# OpenFileWithEagle6_5.net
KiCad netlist of a schematic drawn in EAGLE
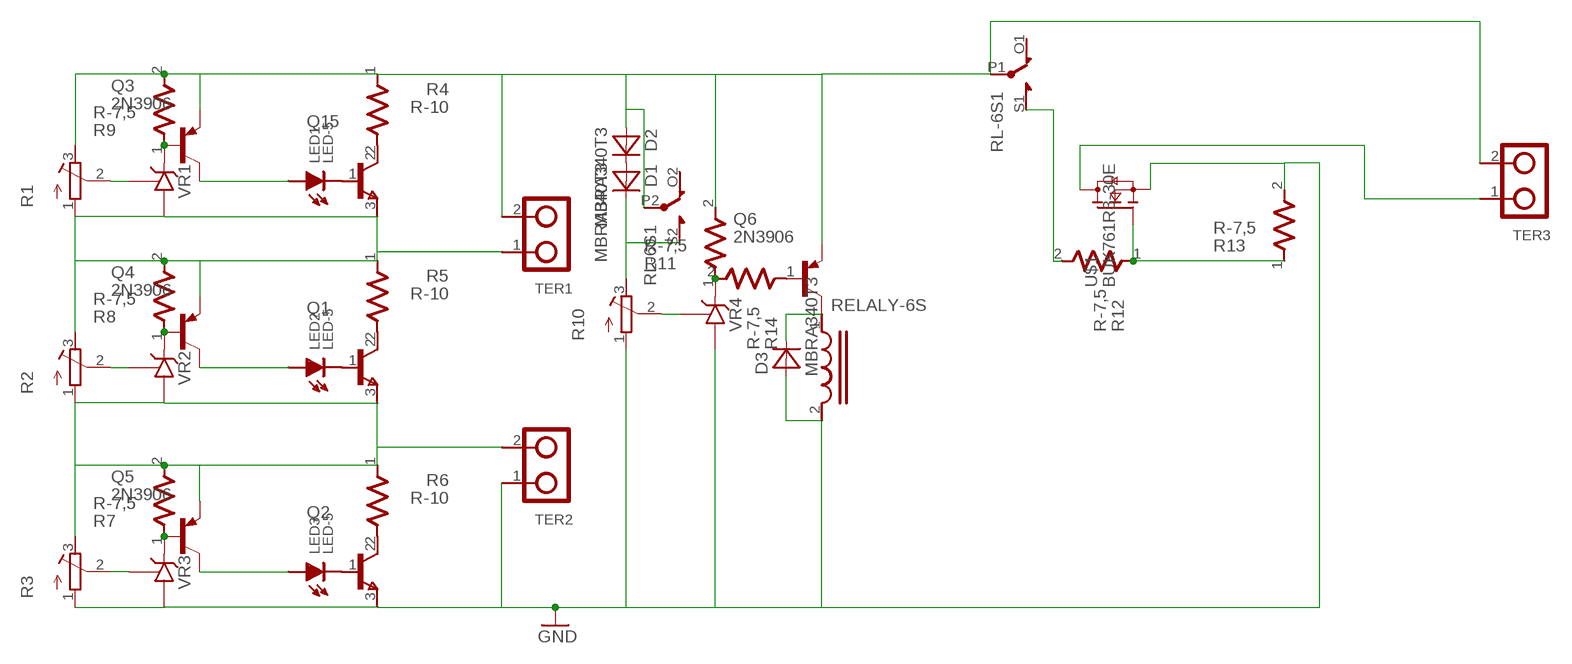
[diagram p0: schematic, sheet 1]

(export (version "E")
  (design (tool "Eeschema 10.0.6"))
  (components
    (comp (ref "D1")
      (value "MBRA340T3")
      (footprint "eagle-import:SMA")
      (libsource (lib "eagle-import") (part "MBRA340T3"))
    )
    (comp (ref "D2")
      (value "MBRA340T3")
      (footprint "eagle-import:SMA")
      (libsource (lib "eagle-import") (part "MBRA340T3"))
    )
    (comp (ref "D3")
      (value "MBRA340T3")
      (footprint "eagle-import:SMA")
      (libsource (lib "eagle-import") (part "MBRA340T3"))
    )
    (comp (ref "LED1")
      (value "LED-5")
      (footprint "eagle-import:LED5")
      (libsource (lib "eagle-import") (part "LED-5"))
    )
    (comp (ref "LED2")
      (value "LED-5")
      (footprint "eagle-import:LED5")
      (libsource (lib "eagle-import") (part "LED-5"))
    )
    (comp (ref "LED3")
      (value "LED-5")
      (footprint "eagle-import:LED5")
      (libsource (lib "eagle-import") (part "LED-5"))
    )
    (comp (ref "Q1")
      (value "C1815")
      (footprint "eagle-import:TO92L")
      (libsource (lib "eagle-import") (part "C1815"))
    )
    (comp (ref "Q2")
      (value "C1815")
      (footprint "eagle-import:TO92L")
      (libsource (lib "eagle-import") (part "C1815"))
    )
    (comp (ref "Q3")
      (value "2N3906")
      (footprint "eagle-import:TO92")
      (libsource (lib "eagle-import") (part "2N3906"))
    )
    (comp (ref "Q4")
      (value "2N3906")
      (footprint "eagle-import:TO92")
      (libsource (lib "eagle-import") (part "2N3906"))
    )
    (comp (ref "Q5")
      (value "2N3906")
      (footprint "eagle-import:TO92")
      (libsource (lib "eagle-import") (part "2N3906"))
    )
    (comp (ref "Q6")
      (value "2N3906")
      (footprint "eagle-import:TO92")
      (libsource (lib "eagle-import") (part "2N3906"))
    )
    (comp (ref "Q15")
      (value "C1815")
      (footprint "eagle-import:TO92L")
      (libsource (lib "eagle-import") (part "C1815"))
    )
    (comp (ref "R1")
      (value "R-TRIMM64W")
      (footprint "eagle-import:RTRIM64W")
      (libsource (lib "eagle-import") (part "R-TRIMM64W"))
    )
    (comp (ref "R2")
      (value "R-TRIMM64W")
      (footprint "eagle-import:RTRIM64W")
      (libsource (lib "eagle-import") (part "R-TRIMM64W"))
    )
    (comp (ref "R3")
      (value "R-TRIMM64W")
      (footprint "eagle-import:RTRIM64W")
      (libsource (lib "eagle-import") (part "R-TRIMM64W"))
    )
    (comp (ref "R4")
      (value "R-10")
      (footprint "eagle-import:R-10")
      (libsource (lib "eagle-import") (part "R-10"))
    )
    (comp (ref "R5")
      (value "R-10")
      (footprint "eagle-import:R-10")
      (libsource (lib "eagle-import") (part "R-10"))
    )
    (comp (ref "R6")
      (value "R-10")
      (footprint "eagle-import:R-10")
      (libsource (lib "eagle-import") (part "R-10"))
    )
    (comp (ref "R7")
      (value "R-7,5")
      (footprint "eagle-import:R-7,5")
      (libsource (lib "eagle-import") (part "R-7,5"))
    )
    (comp (ref "R8")
      (value "R-7,5")
      (footprint "eagle-import:R-7,5")
      (libsource (lib "eagle-import") (part "R-7,5"))
    )
    (comp (ref "R9")
      (value "R-7,5")
      (footprint "eagle-import:R-7,5")
      (libsource (lib "eagle-import") (part "R-7,5"))
    )
    (comp (ref "R10")
      (value "R-TRIMM64W")
      (footprint "eagle-import:RTRIM64W")
      (libsource (lib "eagle-import") (part "R-TRIMM64W"))
    )
    (comp (ref "R11")
      (value "R-7,5")
      (footprint "eagle-import:R-7,5")
      (libsource (lib "eagle-import") (part "R-7,5"))
    )
    (comp (ref "R12")
      (value "R-7,5")
      (footprint "eagle-import:R-7,5")
      (libsource (lib "eagle-import") (part "R-7,5"))
    )
    (comp (ref "R13")
      (value "R-7,5")
      (footprint "eagle-import:R-7,5")
      (libsource (lib "eagle-import") (part "R-7,5"))
    )
    (comp (ref "R14")
      (value "R-7,5")
      (footprint "eagle-import:R-7,5")
      (libsource (lib "eagle-import") (part "R-7,5"))
    )
    (comp (ref "RL-6S1")
      (value "RELALY-6S")
      (footprint "eagle-import:RELAY-6S")
      (libsource (lib "eagle-import") (part "RELALY-6S"))
    )
    (comp (ref "TER1")
      (value "DOMINO-2")
      (footprint "eagle-import:DOMI-2")
      (libsource (lib "eagle-import") (part "DOMINO-2"))
    )
    (comp (ref "TER2")
      (value "DOMINO-2")
      (footprint "eagle-import:DOMI-2")
      (libsource (lib "eagle-import") (part "DOMINO-2"))
    )
    (comp (ref "TER3")
      (value "DOMINO-2")
      (footprint "eagle-import:DOMI-2")
      (libsource (lib "eagle-import") (part "DOMINO-2"))
    )
    (comp (ref "U$1")
      (value "BUK761R3-30E")
      (footprint "eagle-import:SOT404")
      (libsource (lib "eagle-import") (part "BUK761R3-30E"))
    )
    (comp (ref "VR1")
      (value "TL431CLP")
      (footprint "eagle-import:TO92-CLP")
      (libsource (lib "eagle-import") (part "TL431CLP"))
    )
    (comp (ref "VR2")
      (value "TL431CLP")
      (footprint "eagle-import:TO92-CLP")
      (libsource (lib "eagle-import") (part "TL431CLP"))
    )
    (comp (ref "VR3")
      (value "TL431CLP")
      (footprint "eagle-import:TO92-CLP")
      (libsource (lib "eagle-import") (part "TL431CLP"))
    )
    (comp (ref "VR4")
      (value "TL431CLP")
      (footprint "eagle-import:TO92-CLP")
      (libsource (lib "eagle-import") (part "TL431CLP"))
    )
  )
  (nets
    (net (code "1") (name "GND") (class "Default")
      (node (ref "D3") (pin "A") (pinfunction "A_A") (pintype "passive"))
      (node (ref "Q2") (pin "3") (pinfunction "E_3") (pintype "passive"))
      (node (ref "R10") (pin "1") (pinfunction "A_1") (pintype "passive"))
      (node (ref "R13") (pin "2") (pinfunction "2_2") (pintype "passive"))
      (node (ref "R3") (pin "1") (pinfunction "A_1") (pintype "passive"))
      (node (ref "RL-6S1") (pin "2") (pinfunction "2_2") (pintype "bidirectional"))
      (node (ref "TER2") (pin "1") (pinfunction "1_1") (pintype "bidirectional"))
      (node (ref "U$1") (pin "3") (pinfunction "S_3") (pintype "passive"))
      (node (ref "VR3") (pin "A") (pinfunction "A_A") (pintype "passive"))
      (node (ref "VR4") (pin "A") (pinfunction "A_A") (pintype "passive"))
    )
    (net (code "2") (name "Net-(D1-PadA)") (class "Default")
      (node (ref "D1") (pin "A") (pinfunction "A_A") (pintype "passive"))
      (node (ref "D2") (pin "C") (pinfunction "C_C") (pintype "passive"))
    )
    (net (code "3") (name "Net-(Q1-B)") (class "Default")
      (node (ref "LED2") (pin "K") (pinfunction "K_K") (pintype "passive"))
      (node (ref "Q1") (pin "1") (pinfunction "B_1") (pintype "passive"))
    )
    (net (code "4") (name "Net-(Q1-C)") (class "Default")
      (node (ref "Q1") (pin "2") (pinfunction "C_2") (pintype "passive"))
      (node (ref "R5") (pin "2") (pinfunction "3_2") (pintype "passive"))
    )
    (net (code "5") (name "Net-(Q1-E)") (class "Default")
      (node (ref "Q1") (pin "3") (pinfunction "E_3") (pintype "passive"))
      (node (ref "Q5") (pin "3") (pinfunction "E_3") (pintype "passive"))
      (node (ref "R2") (pin "1") (pinfunction "A_1") (pintype "passive"))
      (node (ref "R3") (pin "3") (pinfunction "E_3") (pintype "passive"))
      (node (ref "R6") (pin "1") (pinfunction "1_1") (pintype "passive"))
      (node (ref "R7") (pin "2") (pinfunction "2_2") (pintype "passive"))
      (node (ref "TER2") (pin "2") (pinfunction "2_2") (pintype "bidirectional"))
      (node (ref "VR2") (pin "A") (pinfunction "A_A") (pintype "passive"))
    )
    (net (code "6") (name "Net-(Q2-B)") (class "Default")
      (node (ref "LED3") (pin "K") (pinfunction "K_K") (pintype "passive"))
      (node (ref "Q2") (pin "1") (pinfunction "B_1") (pintype "passive"))
    )
    (net (code "7") (name "Net-(Q2-C)") (class "Default")
      (node (ref "Q2") (pin "2") (pinfunction "C_2") (pintype "passive"))
      (node (ref "R6") (pin "2") (pinfunction "3_2") (pintype "passive"))
    )
    (net (code "8") (name "Net-(Q3-B)") (class "Default")
      (node (ref "Q3") (pin "2") (pinfunction "B_2") (pintype "passive"))
      (node (ref "R9") (pin "1") (pinfunction "1_1") (pintype "passive"))
      (node (ref "VR1") (pin "C") (pinfunction "C_C") (pintype "passive"))
    )
    (net (code "9") (name "Net-(Q3-C)") (class "Default")
      (node (ref "LED1") (pin "A") (pinfunction "A_A") (pintype "passive"))
      (node (ref "Q3") (pin "1") (pinfunction "C_1") (pintype "passive"))
    )
    (net (code "10") (name "Net-(Q3-E)") (class "Default")
      (node (ref "D2") (pin "A") (pinfunction "A_A") (pintype "passive"))
      (node (ref "Q3") (pin "3") (pinfunction "E_3") (pintype "passive"))
      (node (ref "Q6") (pin "3") (pinfunction "E_3") (pintype "passive"))
      (node (ref "R1") (pin "3") (pinfunction "E_3") (pintype "passive"))
      (node (ref "R11") (pin "2") (pinfunction "2_2") (pintype "passive"))
      (node (ref "R4") (pin "1") (pinfunction "1_1") (pintype "passive"))
      (node (ref "R9") (pin "2") (pinfunction "2_2") (pintype "passive"))
      (node (ref "RL-6S1") (pin "P1") (pinfunction "P_P1") (pintype "passive"))
      (node (ref "RL-6S1") (pin "P2") (pinfunction "P_P2") (pintype "passive"))
      (node (ref "TER1") (pin "2") (pinfunction "2_2") (pintype "bidirectional"))
      (node (ref "TER3") (pin "2") (pinfunction "2_2") (pintype "bidirectional"))
    )
    (net (code "11") (name "Net-(Q4-B)") (class "Default")
      (node (ref "Q4") (pin "2") (pinfunction "B_2") (pintype "passive"))
      (node (ref "R8") (pin "1") (pinfunction "1_1") (pintype "passive"))
      (node (ref "VR2") (pin "C") (pinfunction "C_C") (pintype "passive"))
    )
    (net (code "12") (name "Net-(Q4-C)") (class "Default")
      (node (ref "LED2") (pin "A") (pinfunction "A_A") (pintype "passive"))
      (node (ref "Q4") (pin "1") (pinfunction "C_1") (pintype "passive"))
    )
    (net (code "13") (name "Net-(Q5-B)") (class "Default")
      (node (ref "Q5") (pin "2") (pinfunction "B_2") (pintype "passive"))
      (node (ref "R7") (pin "1") (pinfunction "1_1") (pintype "passive"))
      (node (ref "VR3") (pin "C") (pinfunction "C_C") (pintype "passive"))
    )
    (net (code "14") (name "Net-(Q5-C)") (class "Default")
      (node (ref "LED3") (pin "A") (pinfunction "A_A") (pintype "passive"))
      (node (ref "Q5") (pin "1") (pinfunction "C_1") (pintype "passive"))
    )
    (net (code "15") (name "Net-(Q6-B)") (class "Default")
      (node (ref "Q6") (pin "2") (pinfunction "B_2") (pintype "passive"))
      (node (ref "R14") (pin "1") (pinfunction "1_1") (pintype "passive"))
    )
    (net (code "16") (name "Net-(Q6-C)") (class "Default")
      (node (ref "D3") (pin "C") (pinfunction "C_C") (pintype "passive"))
      (node (ref "Q6") (pin "1") (pinfunction "C_1") (pintype "passive"))
      (node (ref "RL-6S1") (pin "1") (pinfunction "1_1") (pintype "bidirectional"))
    )
    (net (code "17") (name "Net-(Q15-B)") (class "Default")
      (node (ref "LED1") (pin "K") (pinfunction "K_K") (pintype "passive"))
      (node (ref "Q15") (pin "1") (pinfunction "B_1") (pintype "passive"))
    )
    (net (code "18") (name "Net-(Q15-C)") (class "Default")
      (node (ref "Q15") (pin "2") (pinfunction "C_2") (pintype "passive"))
      (node (ref "R4") (pin "2") (pinfunction "3_2") (pintype "passive"))
    )
    (net (code "19") (name "Net-(Q15-E)") (class "Default")
      (node (ref "Q15") (pin "3") (pinfunction "E_3") (pintype "passive"))
      (node (ref "Q4") (pin "3") (pinfunction "E_3") (pintype "passive"))
      (node (ref "R1") (pin "1") (pinfunction "A_1") (pintype "passive"))
      (node (ref "R2") (pin "3") (pinfunction "E_3") (pintype "passive"))
      (node (ref "R5") (pin "1") (pinfunction "1_1") (pintype "passive"))
      (node (ref "R8") (pin "2") (pinfunction "2_2") (pintype "passive"))
      (node (ref "TER1") (pin "1") (pinfunction "1_1") (pintype "bidirectional"))
      (node (ref "VR1") (pin "A") (pinfunction "A_A") (pintype "passive"))
    )
    (net (code "20") (name "Net-(R1-S)") (class "Default")
      (node (ref "R1") (pin "2") (pinfunction "S_2") (pintype "passive"))
      (node (ref "VR1") (pin "R") (pinfunction "R_R") (pintype "passive"))
    )
    (net (code "21") (name "Net-(R2-S)") (class "Default")
      (node (ref "R2") (pin "2") (pinfunction "S_2") (pintype "passive"))
      (node (ref "VR2") (pin "R") (pinfunction "R_R") (pintype "passive"))
    )
    (net (code "22") (name "Net-(R3-S)") (class "Default")
      (node (ref "R3") (pin "2") (pinfunction "S_2") (pintype "passive"))
      (node (ref "VR3") (pin "R") (pinfunction "R_R") (pintype "passive"))
    )
    (net (code "23") (name "Net-(R10-E)") (class "Default")
      (node (ref "D1") (pin "C") (pinfunction "C_C") (pintype "passive"))
      (node (ref "R10") (pin "3") (pinfunction "E_3") (pintype "passive"))
      (node (ref "RL-6S1") (pin "S2") (pinfunction "S_S2") (pintype "passive"))
    )
    (net (code "24") (name "Net-(R10-S)") (class "Default")
      (node (ref "R10") (pin "2") (pinfunction "S_2") (pintype "passive"))
      (node (ref "VR4") (pin "R") (pinfunction "R_R") (pintype "passive"))
    )
    (net (code "25") (name "Net-(R11-Pad1)") (class "Default")
      (node (ref "R11") (pin "1") (pinfunction "1_1") (pintype "passive"))
      (node (ref "R14") (pin "2") (pinfunction "2_2") (pintype "passive"))
      (node (ref "VR4") (pin "C") (pinfunction "C_C") (pintype "passive"))
    )
    (net (code "26") (name "Net-(RL-6S1A-S)") (class "Default")
      (node (ref "R12") (pin "2") (pinfunction "2_2") (pintype "passive"))
      (node (ref "RL-6S1") (pin "S1") (pinfunction "S_S1") (pintype "passive"))
    )
    (net (code "27") (name "Net-(U$1-D)") (class "Default")
      (node (ref "TER3") (pin "1") (pinfunction "1_1") (pintype "bidirectional"))
      (node (ref "U$1") (pin "MB") (pinfunction "D_MB") (pintype "passive"))
    )
    (net (code "28") (name "Net-(U$1-G)") (class "Default")
      (node (ref "R12") (pin "1") (pinfunction "1_1") (pintype "passive"))
      (node (ref "R13") (pin "1") (pinfunction "1_1") (pintype "passive"))
      (node (ref "U$1") (pin "1") (pinfunction "G_1") (pintype "passive"))
    )
    (net (code "29") (name "unconnected-(RL-6S1A-O-PadO1)") (class "Default")
      (node (ref "RL-6S1") (pin "O1") (pinfunction "O_O1") (pintype "passive"))
    )
    (net (code "30") (name "unconnected-(RL-6S1B-O-PadO2)") (class "Default")
      (node (ref "RL-6S1") (pin "O2") (pinfunction "O_O2") (pintype "passive"))
    )
  )
)
